# v0.net
KiCad netlist of a schematic drawn in EAGLE
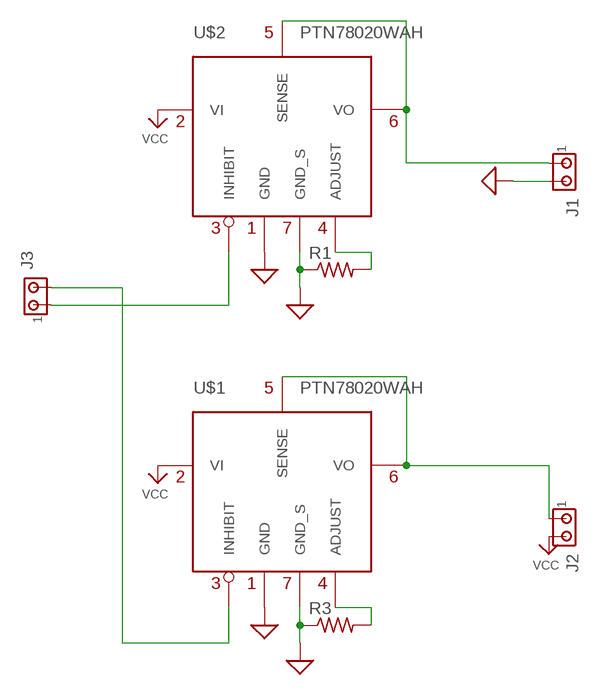
[diagram p0: schematic, sheet 1]

(export (version "E")
  (design (tool "Eeschema 10.0.6"))
  (components
    (comp (ref "J1")
      (value "MTA02-156")
      (footprint "eagle-import:MYJUMPER")
      (libsource (lib "eagle-import") (part "MTA02-156"))
    )
    (comp (ref "J2")
      (value "MTA02-156")
      (footprint "eagle-import:MYJUMPER")
      (libsource (lib "eagle-import") (part "MTA02-156"))
    )
    (comp (ref "J3")
      (value "MTA02-156")
      (footprint "eagle-import:MYJUMPER")
      (libsource (lib "eagle-import") (part "MTA02-156"))
    )
    (comp (ref "R1")
      (value "FLIPFLOP-RES")
      (footprint "eagle-import:0805-THM")
      (libsource (lib "eagle-import") (part "FLIPFLOP-RES"))
    )
    (comp (ref "R3")
      (value "FLIPFLOP-RES")
      (footprint "eagle-import:0805-THM")
      (libsource (lib "eagle-import") (part "FLIPFLOP-RES"))
    )
    (comp (ref "U$1")
      (value "PTN78020WAH")
      (footprint "eagle-import:PTN78020WAH")
      (libsource (lib "eagle-import") (part "PTN78020WAH"))
    )
    (comp (ref "U$2")
      (value "PTN78020WAH")
      (footprint "eagle-import:PTN78020WAH")
      (libsource (lib "eagle-import") (part "PTN78020WAH"))
    )
  )
  (nets
    (net (code "1") (name "Net-(U$1-ADJUST)") (class "Default")
      (node (ref "R3") (pin "2") (pinfunction "2_2") (pintype "passive"))
      (node (ref "U$1") (pin "4") (pinfunction "ADJUST_4") (pintype "bidirectional"))
    )
    (net (code "2") (name "Net-(U$1-INHIBIT)") (class "Default")
      (node (ref "J3") (pin "2") (pinfunction "2_2") (pintype "passive"))
      (node (ref "U$1") (pin "3") (pinfunction "INHIBIT_3") (pintype "bidirectional"))
    )
    (net (code "3") (name "Net-(U$1-SENSE)") (class "Default")
      (node (ref "J2") (pin "1") (pinfunction "1_1") (pintype "passive"))
      (node (ref "U$1") (pin "5") (pinfunction "SENSE_5") (pintype "bidirectional"))
      (node (ref "U$1") (pin "6") (pinfunction "VO_6") (pintype "bidirectional"))
    )
    (net (code "4") (name "Net-(U$2-ADJUST)") (class "Default")
      (node (ref "R1") (pin "2") (pinfunction "2_2") (pintype "passive"))
      (node (ref "U$2") (pin "4") (pinfunction "ADJUST_4") (pintype "bidirectional"))
    )
    (net (code "5") (name "Net-(U$2-INHIBIT)") (class "Default")
      (node (ref "J3") (pin "1") (pinfunction "1_1") (pintype "passive"))
      (node (ref "U$2") (pin "3") (pinfunction "INHIBIT_3") (pintype "bidirectional"))
    )
    (net (code "6") (name "Net-(U$2-SENSE)") (class "Default")
      (node (ref "J1") (pin "1") (pinfunction "1_1") (pintype "passive"))
      (node (ref "U$2") (pin "5") (pinfunction "SENSE_5") (pintype "bidirectional"))
      (node (ref "U$2") (pin "6") (pinfunction "VO_6") (pintype "bidirectional"))
    )
    (net (code "7") (name "SUP") (class "Default")
      (node (ref "J1") (pin "2") (pinfunction "2_2") (pintype "passive"))
      (node (ref "R1") (pin "1") (pinfunction "1_1") (pintype "passive"))
      (node (ref "R3") (pin "1") (pinfunction "1_1") (pintype "passive"))
      (node (ref "U$1") (pin "1") (pinfunction "GND_1") (pintype "bidirectional"))
      (node (ref "U$1") (pin "7") (pinfunction "GND_S_7") (pintype "bidirectional"))
      (node (ref "U$2") (pin "1") (pinfunction "GND_1") (pintype "bidirectional"))
      (node (ref "U$2") (pin "7") (pinfunction "GND_S_7") (pintype "bidirectional"))
    )
    (net (code "8") (name "VCC") (class "Default")
      (node (ref "J2") (pin "2") (pinfunction "2_2") (pintype "passive"))
      (node (ref "U$1") (pin "2") (pinfunction "VI_2") (pintype "bidirectional"))
      (node (ref "U$2") (pin "2") (pinfunction "VI_2") (pintype "bidirectional"))
    )
  )
)
